# TCGaugeAmplifier.net
KiCad netlist of a schematic drawn in EAGLE
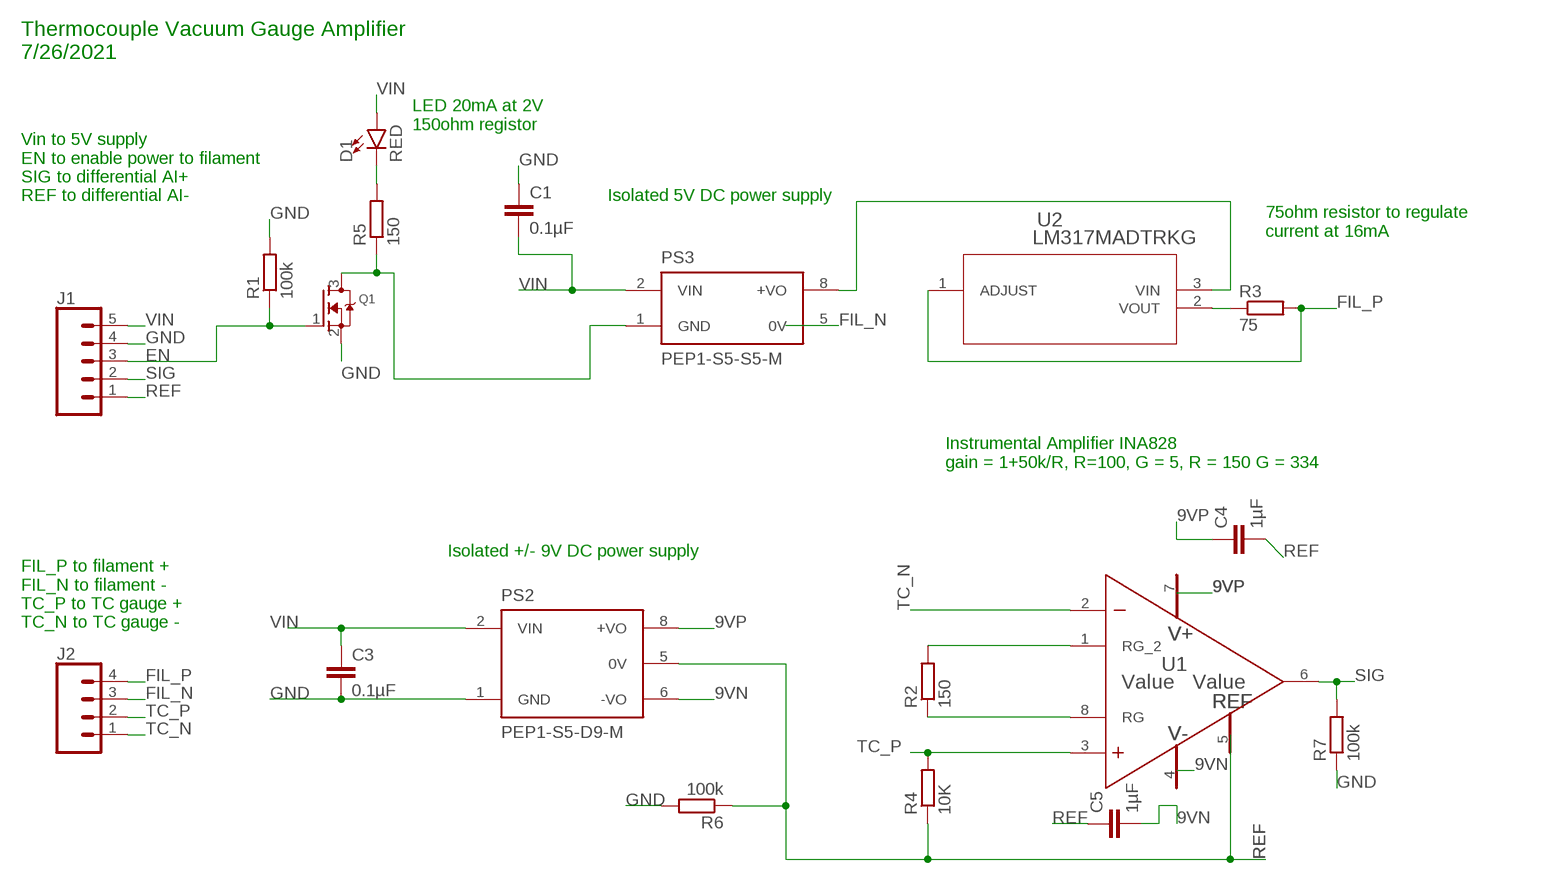
[diagram p0: schematic, sheet 1]

(export (version "E")
  (design (tool "Eeschema 10.0.6"))
  (components
    (comp (ref "C1")
      (value "0.1µF")
      (footprint "eagle-import:0805")
      (libsource (lib "eagle-import") (part "0.33UF/330NF-0805-50V-10%"))
    )
    (comp (ref "C3")
      (value "0.1µF")
      (footprint "eagle-import:0805")
      (libsource (lib "eagle-import") (part "0.33UF/330NF-0805-50V-10%"))
    )
    (comp (ref "C4")
      (value "1µF")
      (footprint "eagle-import:0805")
      (libsource (lib "eagle-import") (part "0.33UF/330NF-0805-50V-10%"))
    )
    (comp (ref "C5")
      (value "1µF")
      (footprint "eagle-import:0805")
      (libsource (lib "eagle-import") (part "0.33UF/330NF-0805-50V-10%"))
    )
    (comp (ref "D1")
      (value "RED")
      (footprint "eagle-import:LED-0603")
      (libsource (lib "eagle-import") (part "LED-RED0603"))
    )
    (comp (ref "J1")
      (value "CONN_05")
      (footprint "eagle-import:1X05")
      (libsource (lib "eagle-import") (part "CONN_05"))
    )
    (comp (ref "J2")
      (value "CONN_04")
      (footprint "eagle-import:1X04")
      (libsource (lib "eagle-import") (part "CONN_04"))
    )
    (comp (ref "PS2")
      (value "PEP1-S5-D9-M")
      (footprint "eagle-import:CONV_PEP1-S5-D9-M")
      (fields (field (name "MANUFACTURER") "CUI Inc."))
      (libsource (lib "eagle-import") (part "PEP1-S5-D9-M"))
    )
    (comp (ref "PS3")
      (value "PEP1-S5-S5-M")
      (footprint "eagle-import:CONV_PEP1-S5-S5-M")
      (fields (field (name "MANUFACTURER") "CUI Inc."))
      (libsource (lib "eagle-import") (part "PEP1-S5-S5-M"))
    )
    (comp (ref "Q1")
      (value "MOSFET-NREFLOW")
      (footprint "eagle-import:SOT23")
      (libsource (lib "eagle-import") (part "MOSFET-NREFLOW"))
    )
    (comp (ref "R1")
      (value "100k")
      (footprint "eagle-import:R0805")
      (libsource (lib "eagle-import") (part "R-EU_R0805"))
    )
    (comp (ref "R2")
      (value "150")
      (footprint "eagle-import:R0805")
      (libsource (lib "eagle-import") (part "R-EU_R0805"))
    )
    (comp (ref "R3")
      (value "75")
      (footprint "eagle-import:R0805")
      (libsource (lib "eagle-import") (part "R-EU_R0805"))
    )
    (comp (ref "R4")
      (value "10K")
      (footprint "eagle-import:R0805")
      (libsource (lib "eagle-import") (part "R-EU_R0805"))
    )
    (comp (ref "R5")
      (value "150")
      (footprint "eagle-import:R0805")
      (libsource (lib "eagle-import") (part "R-EU_R0805"))
    )
    (comp (ref "R6")
      (value "100k")
      (footprint "eagle-import:R0805")
      (libsource (lib "eagle-import") (part "R-EU_R0805"))
    )
    (comp (ref "R7")
      (value "100k")
      (footprint "eagle-import:R0805")
      (libsource (lib "eagle-import") (part "R-EU_R0805"))
    )
    (comp (ref "U1")
      (value "Value")
      (footprint "eagle-import:D0008A_N")
      (fields (field (name "MANUFACTURER") "Texas Instruments") (field (name "PARTNUMBER") "INA828IDR"))
      (libsource (lib "eagle-import") (part "INA828IDR"))
    )
    (comp (ref "U2")
      (value "LM317MADTRKG")
      (footprint "eagle-import:DPAK-3_ONS")
      (fields (field (name "COPYRIGHT") "Copyright (C) 2016 Accelerated Designs. All rights reserved"))
      (libsource (lib "eagle-import") (part "LM317MADTRKG"))
    )
  )
  (nets
    (net (code "1") (name "/9VN") (class "Default")
      (node (ref "C5") (pin "2") (pinfunction "2_2") (pintype "passive"))
      (node (ref "PS2") (pin "6") (pinfunction "-VO_6") (pintype "output"))
      (node (ref "U1") (pin "4") (pinfunction "V-_4") (pintype "power_in"))
    )
    (net (code "2") (name "/9VP") (class "Default")
      (node (ref "C4") (pin "1") (pinfunction "1_1") (pintype "passive"))
      (node (ref "PS2") (pin "8") (pinfunction "+VO_8") (pintype "output"))
      (node (ref "U1") (pin "7") (pinfunction "V+_7") (pintype "power_in"))
    )
    (net (code "3") (name "/EN") (class "Default")
      (node (ref "J1") (pin "3") (pinfunction "3_3") (pintype "passive"))
      (node (ref "Q1") (pin "1") (pinfunction "G_1") (pintype "bidirectional"))
      (node (ref "R1") (pin "1") (pinfunction "1_1") (pintype "passive"))
    )
    (net (code "4") (name "/FIL_N") (class "Default")
      (node (ref "J2") (pin "3") (pinfunction "3_3") (pintype "passive"))
      (node (ref "PS3") (pin "5") (pinfunction "0V_5") (pintype "output"))
    )
    (net (code "5") (name "/FIL_P") (class "Default")
      (node (ref "J2") (pin "4") (pinfunction "4_4") (pintype "passive"))
      (node (ref "R3") (pin "2") (pinfunction "2_2") (pintype "passive"))
      (node (ref "U2") (pin "1") (pinfunction "ADJUST_1") (pintype "passive"))
    )
    (net (code "6") (name "/GND") (class "Default")
      (node (ref "C1") (pin "1") (pinfunction "1_1") (pintype "passive"))
      (node (ref "C3") (pin "2") (pinfunction "2_2") (pintype "passive"))
      (node (ref "J1") (pin "4") (pinfunction "4_4") (pintype "passive"))
      (node (ref "PS2") (pin "1") (pinfunction "GND_1") (pintype "power_in"))
      (node (ref "Q1") (pin "2") (pinfunction "S_2") (pintype "bidirectional"))
      (node (ref "R1") (pin "2") (pinfunction "2_2") (pintype "passive"))
      (node (ref "R6") (pin "2") (pinfunction "2_2") (pintype "passive"))
      (node (ref "R7") (pin "1") (pinfunction "1_1") (pintype "passive"))
    )
    (net (code "7") (name "/REF") (class "Default")
      (node (ref "C4") (pin "2") (pinfunction "2_2") (pintype "passive"))
      (node (ref "C5") (pin "1") (pinfunction "1_1") (pintype "passive"))
      (node (ref "J1") (pin "1") (pinfunction "1_1") (pintype "passive"))
      (node (ref "PS2") (pin "5") (pinfunction "0V_5") (pintype "output"))
      (node (ref "R4") (pin "1") (pinfunction "1_1") (pintype "passive"))
      (node (ref "R6") (pin "1") (pinfunction "1_1") (pintype "passive"))
      (node (ref "U1") (pin "5") (pinfunction "REF_5") (pintype "input"))
    )
    (net (code "8") (name "/SIG") (class "Default")
      (node (ref "J1") (pin "2") (pinfunction "2_2") (pintype "passive"))
      (node (ref "R7") (pin "2") (pinfunction "2_2") (pintype "passive"))
      (node (ref "U1") (pin "6") (pinfunction "OUT_6") (pintype "output"))
    )
    (net (code "9") (name "/TC_N") (class "Default")
      (node (ref "J2") (pin "1") (pinfunction "1_1") (pintype "passive"))
      (node (ref "U1") (pin "2") (pinfunction "IN-_2") (pintype "input"))
    )
    (net (code "10") (name "/TC_P") (class "Default")
      (node (ref "J2") (pin "2") (pinfunction "2_2") (pintype "passive"))
      (node (ref "R4") (pin "2") (pinfunction "2_2") (pintype "passive"))
      (node (ref "U1") (pin "3") (pinfunction "IN+_3") (pintype "input"))
    )
    (net (code "11") (name "/VIN") (class "Default")
      (node (ref "C1") (pin "2") (pinfunction "2_2") (pintype "passive"))
      (node (ref "C3") (pin "1") (pinfunction "1_1") (pintype "passive"))
      (node (ref "D1") (pin "A") (pinfunction "A_A") (pintype "passive"))
      (node (ref "J1") (pin "5") (pinfunction "5_5") (pintype "passive"))
      (node (ref "PS2") (pin "2") (pinfunction "VIN_2") (pintype "input"))
      (node (ref "PS3") (pin "2") (pinfunction "VIN_2") (pintype "input"))
    )
    (net (code "12") (name "Net-(D1-PadC)") (class "Default")
      (node (ref "D1") (pin "C") (pinfunction "C_C") (pintype "passive"))
      (node (ref "R5") (pin "2") (pinfunction "2_2") (pintype "passive"))
    )
    (net (code "13") (name "Net-(PS3-+VO)") (class "Default")
      (node (ref "PS3") (pin "8") (pinfunction "+VO_8") (pintype "output"))
      (node (ref "U2") (pin "3") (pinfunction "VIN_3") (pintype "input"))
    )
    (net (code "14") (name "Net-(PS3-GND)") (class "Default")
      (node (ref "PS3") (pin "1") (pinfunction "GND_1") (pintype "power_in"))
      (node (ref "Q1") (pin "3") (pinfunction "D_3") (pintype "bidirectional"))
      (node (ref "R5") (pin "1") (pinfunction "1_1") (pintype "passive"))
    )
    (net (code "15") (name "Net-(U1-RG)") (class "Default")
      (node (ref "R2") (pin "1") (pinfunction "1_1") (pintype "passive"))
      (node (ref "U1") (pin "8") (pinfunction "RG_8") (pintype "passive"))
    )
    (net (code "16") (name "Net-(U1-RG_2)") (class "Default")
      (node (ref "R2") (pin "2") (pinfunction "2_2") (pintype "passive"))
      (node (ref "U1") (pin "1") (pinfunction "RG_2_1") (pintype "passive"))
    )
    (net (code "17") (name "Net-(U2-VOUT)") (class "Default")
      (node (ref "R3") (pin "1") (pinfunction "1_1") (pintype "passive"))
      (node (ref "U2") (pin "2") (pinfunction "VOUT_2") (pintype "output"))
    )
  )
)
